# DD2090_4CAM_FFC_BOOT_JTAG_SD.net
KiCad netlist of a schematic drawn in Altium Designer
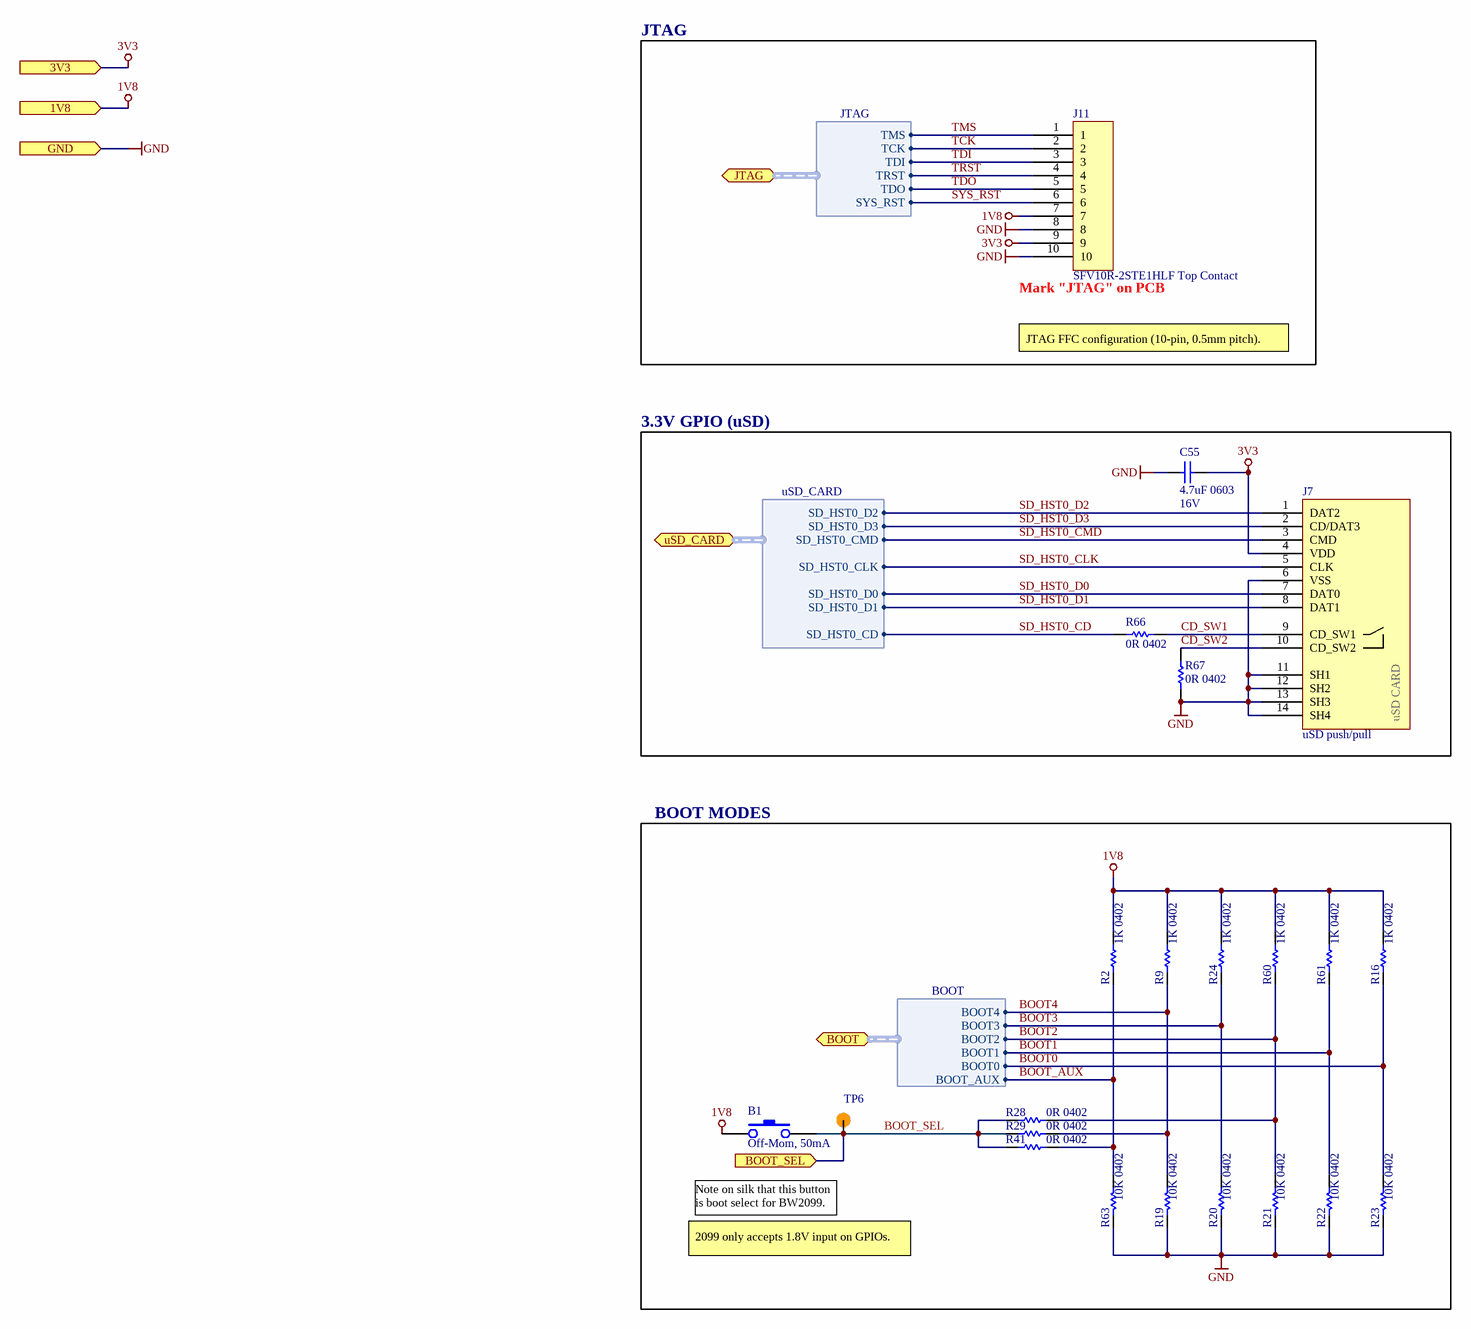
[diagram p0: DD2090_4CAM_FFC_BOOT_JTAG_SD.SchDoc]

(export (version "E")
  (design (tool "Eeschema 10.0.6"))
  (components
    (comp (ref "B1")
      (value "Off-Mom, 50mA")
      (footprint "LuxonisMaster:DTSM-32N-V")
      (description "SWITCH TACTILE SMT 3.5mm * 6mm , brown 160gf")
      (libsource (lib "LuxonisMaster") (part "DTSM-32N-V"))
    )
    (comp (ref "C55")
      (value "4.7uF 0603")
      (footprint "CAPC0603(1608)100_N")
      (description "CAP CER 4.7UF 16V X5R 0603 10%")
      (fields (field (name "TOLERANCE") "10%") (field (name "VOLTAGE RATING") "16V"))
      (libsource (lib "LuxonisMaster") (part "GRM188R61C475KAAJD"))
    )
    (comp (ref "J7")
      (value "uSD push/pull")
      (footprint "LuxonisMaster:104031-0811")
      (description "CONN MICRO SD CARD PUSH-PULL R/A")
      (libsource (lib "LuxonisMaster") (part "104031-0811"))
    )
    (comp (ref "J11")
      (value "SFV10R-2STE1HLF Top Contact")
      (footprint "LuxonisMaster:SFV10R-2STE1HLF")
      (description "CONN FFC TOP 10POS 0.50MM R/A")
      (libsource (lib "LuxonisMaster") (part "SFV10R-2STE1HLF"))
    )
    (comp (ref "R2")
      (value "1K 0402")
      (footprint "RESC0402(1005)_N")
      (fields (field (name "TOLERANCE") "1%"))
      (libsource (lib "LuxonisMaster") (part "RC0402FR-071KL"))
    )
    (comp (ref "R9")
      (value "1K 0402")
      (footprint "RESC0402(1005)_N")
      (fields (field (name "TOLERANCE") "1%"))
      (libsource (lib "LuxonisMaster") (part "RC0402FR-071KL"))
    )
    (comp (ref "R16")
      (value "1K 0402")
      (footprint "RESC0402(1005)_N")
      (fields (field (name "TOLERANCE") "1%"))
      (libsource (lib "LuxonisMaster") (part "RC0402FR-071KL"))
    )
    (comp (ref "R19")
      (value "10K 0402")
      (footprint "RESC0402(1005)_N")
      (fields (field (name "TOLERANCE") "1%"))
      (libsource (lib "LuxonisMaster") (part "RC0402FR-1310KL"))
    )
    (comp (ref "R20")
      (value "10K 0402")
      (footprint "RESC0402(1005)_N")
      (fields (field (name "TOLERANCE") "1%"))
      (libsource (lib "LuxonisMaster") (part "RC0402FR-1310KL"))
    )
    (comp (ref "R21")
      (value "10K 0402")
      (footprint "RESC0402(1005)_N")
      (fields (field (name "TOLERANCE") "1%"))
      (libsource (lib "LuxonisMaster") (part "RC0402FR-1310KL"))
    )
    (comp (ref "R22")
      (value "10K 0402")
      (footprint "RESC0402(1005)_N")
      (fields (field (name "TOLERANCE") "1%"))
      (libsource (lib "LuxonisMaster") (part "RC0402FR-1310KL"))
    )
    (comp (ref "R23")
      (value "10K 0402")
      (footprint "RESC0402(1005)_N")
      (fields (field (name "TOLERANCE") "1%"))
      (libsource (lib "LuxonisMaster") (part "RC0402FR-1310KL"))
    )
    (comp (ref "R24")
      (value "1K 0402")
      (footprint "RESC0402(1005)_N")
      (fields (field (name "TOLERANCE") "1%"))
      (libsource (lib "LuxonisMaster") (part "RC0402FR-071KL"))
    )
    (comp (ref "R28")
      (value "0R 0402")
      (footprint "RESC0402(1005)_N")
      (description "RES SMD 0 OHM JUMPER 1/16W 0402")
      (fields (field (name "TOLERANCE") "5%"))
      (libsource (lib "LuxonisMaster") (part "CRCW04020000Z0ED"))
    )
    (comp (ref "R29")
      (value "0R 0402")
      (footprint "RESC0402(1005)_N")
      (description "RES SMD 0 OHM JUMPER 1/16W 0402")
      (fields (field (name "TOLERANCE") "5%"))
      (libsource (lib "LuxonisMaster") (part "CRCW04020000Z0ED"))
    )
    (comp (ref "R41")
      (value "0R 0402")
      (footprint "RESC0402(1005)_N")
      (description "RES SMD 0 OHM JUMPER 1/16W 0402")
      (fields (field (name "TOLERANCE") "5%"))
      (libsource (lib "LuxonisMaster") (part "CRCW04020000Z0ED"))
    )
    (comp (ref "R60")
      (value "1K 0402")
      (footprint "RESC0402(1005)_N")
      (fields (field (name "TOLERANCE") "1%"))
      (libsource (lib "LuxonisMaster") (part "RC0402FR-071KL"))
    )
    (comp (ref "R61")
      (value "1K 0402")
      (footprint "RESC0402(1005)_N")
      (fields (field (name "TOLERANCE") "1%"))
      (libsource (lib "LuxonisMaster") (part "RC0402FR-071KL"))
    )
    (comp (ref "R63")
      (value "10K 0402")
      (footprint "RESC0402(1005)_N")
      (fields (field (name "TOLERANCE") "1%"))
      (libsource (lib "LuxonisMaster") (part "RC0402FR-1310KL"))
    )
    (comp (ref "R66")
      (value "0R 0402")
      (footprint "RESC0402(1005)_N")
      (description "RES SMD 0 OHM JUMPER 1/16W 0402")
      (fields (field (name "TOLERANCE") "5%"))
      (libsource (lib "LuxonisMaster") (part "CRCW04020000Z0ED"))
    )
    (comp (ref "R67")
      (value "0R 0402")
      (footprint "RESC0402(1005)_N")
      (description "RES SMD 0 OHM JUMPER 1/16W 0402")
      (fields (field (name "TOLERANCE") "5%"))
      (libsource (lib "LuxonisMaster") (part "CRCW04020000Z0ED"))
    )
    (comp (ref "TP6")
      (value "TP100_200_NS")
      (footprint "LuxonisMaster:TP100_200_NS")
      (libsource (lib "LuxonisMaster") (part "TEST_POINT"))
    )
  )
  (nets
    (net (code "4") (name "/BOOT0") (class "Default")
      (node (ref "R16") (pin "1") (pinfunction "1_1") (pintype "passive"))
      (node (ref "R23") (pin "1") (pinfunction "1_1") (pintype "passive"))
    )
    (net (code "5") (name "/BOOT1") (class "Default")
      (node (ref "R22") (pin "1") (pinfunction "1_1") (pintype "passive"))
      (node (ref "R61") (pin "1") (pinfunction "1_1") (pintype "passive"))
    )
    (net (code "6") (name "/BOOT2") (class "Default")
      (node (ref "R21") (pin "1") (pinfunction "1_1") (pintype "passive"))
      (node (ref "R28") (pin "1") (pinfunction "1_1") (pintype "passive"))
      (node (ref "R60") (pin "1") (pinfunction "1_1") (pintype "passive"))
    )
    (net (code "7") (name "/BOOT3") (class "Default")
      (node (ref "R20") (pin "1") (pinfunction "1_1") (pintype "passive"))
      (node (ref "R24") (pin "1") (pinfunction "1_1") (pintype "passive"))
    )
    (net (code "8") (name "/BOOT4") (class "Default")
      (node (ref "R19") (pin "1") (pinfunction "1_1") (pintype "passive"))
      (node (ref "R29") (pin "1") (pinfunction "1_1") (pintype "passive"))
      (node (ref "R9") (pin "1") (pinfunction "1_1") (pintype "passive"))
    )
    (net (code "9") (name "/BOOT_AUX") (class "Default")
      (node (ref "R2") (pin "1") (pinfunction "1_1") (pintype "passive"))
      (node (ref "R41") (pin "1") (pinfunction "1_1") (pintype "passive"))
      (node (ref "R63") (pin "1") (pinfunction "1_1") (pintype "passive"))
    )
    (net (code "10") (name "/BOOT_SEL") (class "Default")
      (node (ref "B1") (pin "2") (pinfunction "2_2") (pintype "passive"))
      (node (ref "R28") (pin "2") (pinfunction "2_2") (pintype "passive"))
      (node (ref "R29") (pin "2") (pinfunction "2_2") (pintype "passive"))
      (node (ref "R41") (pin "2") (pinfunction "2_2") (pintype "passive"))
      (node (ref "TP6") (pin "1") (pintype "passive"))
    )
    (net (code "11") (name "/CD_SW1") (class "Default")
      (node (ref "J7") (pin "9") (pinfunction "CD_SW1_9") (pintype "passive"))
      (node (ref "R66") (pin "1") (pinfunction "1_1") (pintype "passive"))
    )
    (net (code "12") (name "/CD_SW2") (class "Default")
      (node (ref "J7") (pin "10") (pinfunction "CD_SW2_10") (pintype "passive"))
      (node (ref "R67") (pin "2") (pinfunction "2_2") (pintype "passive"))
    )
    (net (code "13") (name "/SD_HST0_CD") (class "Default")
      (node (ref "R66") (pin "2") (pinfunction "2_2") (pintype "passive"))
    )
    (net (code "14") (name "/SD_HST0_CLK") (class "Default")
      (node (ref "J7") (pin "5") (pinfunction "CLK_5") (pintype "passive"))
    )
    (net (code "15") (name "/SD_HST0_CMD") (class "Default")
      (node (ref "J7") (pin "3") (pinfunction "CMD_3") (pintype "passive"))
    )
    (net (code "16") (name "/SD_HST0_D0") (class "Default")
      (node (ref "J7") (pin "7") (pinfunction "DAT0_7") (pintype "passive"))
    )
    (net (code "17") (name "/SD_HST0_D1") (class "Default")
      (node (ref "J7") (pin "8") (pinfunction "DAT1_8") (pintype "passive"))
    )
    (net (code "18") (name "/SD_HST0_D2") (class "Default")
      (node (ref "J7") (pin "1") (pinfunction "DAT2_1") (pintype "passive"))
    )
    (net (code "19") (name "/SD_HST0_D3") (class "Default")
      (node (ref "J7") (pin "2") (pinfunction "CD/DAT3_2") (pintype "passive"))
    )
    (net (code "20") (name "/SYS_RST") (class "Default")
      (node (ref "J11") (pin "6") (pinfunction "6_6") (pintype "passive"))
    )
    (net (code "21") (name "/TCK") (class "Default")
      (node (ref "J11") (pin "2") (pinfunction "2_2") (pintype "passive"))
    )
    (net (code "22") (name "/TDI") (class "Default")
      (node (ref "J11") (pin "3") (pinfunction "3_3") (pintype "passive"))
    )
    (net (code "23") (name "/TDO") (class "Default")
      (node (ref "J11") (pin "5") (pinfunction "5_5") (pintype "passive"))
    )
    (net (code "24") (name "/TMS") (class "Default")
      (node (ref "J11") (pin "1") (pinfunction "1_1") (pintype "passive"))
    )
    (net (code "25") (name "/TRST") (class "Default")
      (node (ref "J11") (pin "4") (pinfunction "4_4") (pintype "passive"))
    )
    (net (code "29") (name "1V8") (class "Default")
      (node (ref "B1") (pin "1") (pinfunction "1_1") (pintype "passive"))
      (node (ref "J11") (pin "7") (pinfunction "7_7") (pintype "passive"))
      (node (ref "R16") (pin "2") (pinfunction "2_2") (pintype "passive"))
      (node (ref "R2") (pin "2") (pinfunction "2_2") (pintype "passive"))
      (node (ref "R24") (pin "2") (pinfunction "2_2") (pintype "passive"))
      (node (ref "R60") (pin "2") (pinfunction "2_2") (pintype "passive"))
      (node (ref "R61") (pin "2") (pinfunction "2_2") (pintype "passive"))
      (node (ref "R9") (pin "2") (pinfunction "2_2") (pintype "passive"))
    )
    (net (code "30") (name "3V3") (class "Default")
      (node (ref "C55") (pin "2") (pinfunction "2_2") (pintype "passive"))
      (node (ref "J11") (pin "9") (pinfunction "9_9") (pintype "passive"))
      (node (ref "J7") (pin "4") (pinfunction "VDD_4") (pintype "passive"))
    )
    (net (code "31") (name "GND") (class "Default")
      (node (ref "C55") (pin "1") (pinfunction "1_1") (pintype "passive"))
      (node (ref "J11") (pin "10") (pinfunction "10_10") (pintype "passive"))
      (node (ref "J11") (pin "8") (pinfunction "8_8") (pintype "passive"))
      (node (ref "J7") (pin "11") (pinfunction "SH1_11") (pintype "passive"))
      (node (ref "J7") (pin "12") (pinfunction "SH2_12") (pintype "passive"))
      (node (ref "J7") (pin "13") (pinfunction "SH3_13") (pintype "passive"))
      (node (ref "J7") (pin "14") (pinfunction "SH4_14") (pintype "passive"))
      (node (ref "J7") (pin "6") (pinfunction "VSS_6") (pintype "passive"))
      (node (ref "R19") (pin "2") (pinfunction "2_2") (pintype "passive"))
      (node (ref "R20") (pin "2") (pinfunction "2_2") (pintype "passive"))
      (node (ref "R21") (pin "2") (pinfunction "2_2") (pintype "passive"))
      (node (ref "R22") (pin "2") (pinfunction "2_2") (pintype "passive"))
      (node (ref "R23") (pin "2") (pinfunction "2_2") (pintype "passive"))
      (node (ref "R63") (pin "2") (pinfunction "2_2") (pintype "passive"))
      (node (ref "R67") (pin "1") (pinfunction "1_1") (pintype "passive"))
    )
  )
)
